# Sheet1.net
KiCad netlist of a schematic drawn in Altium Designer
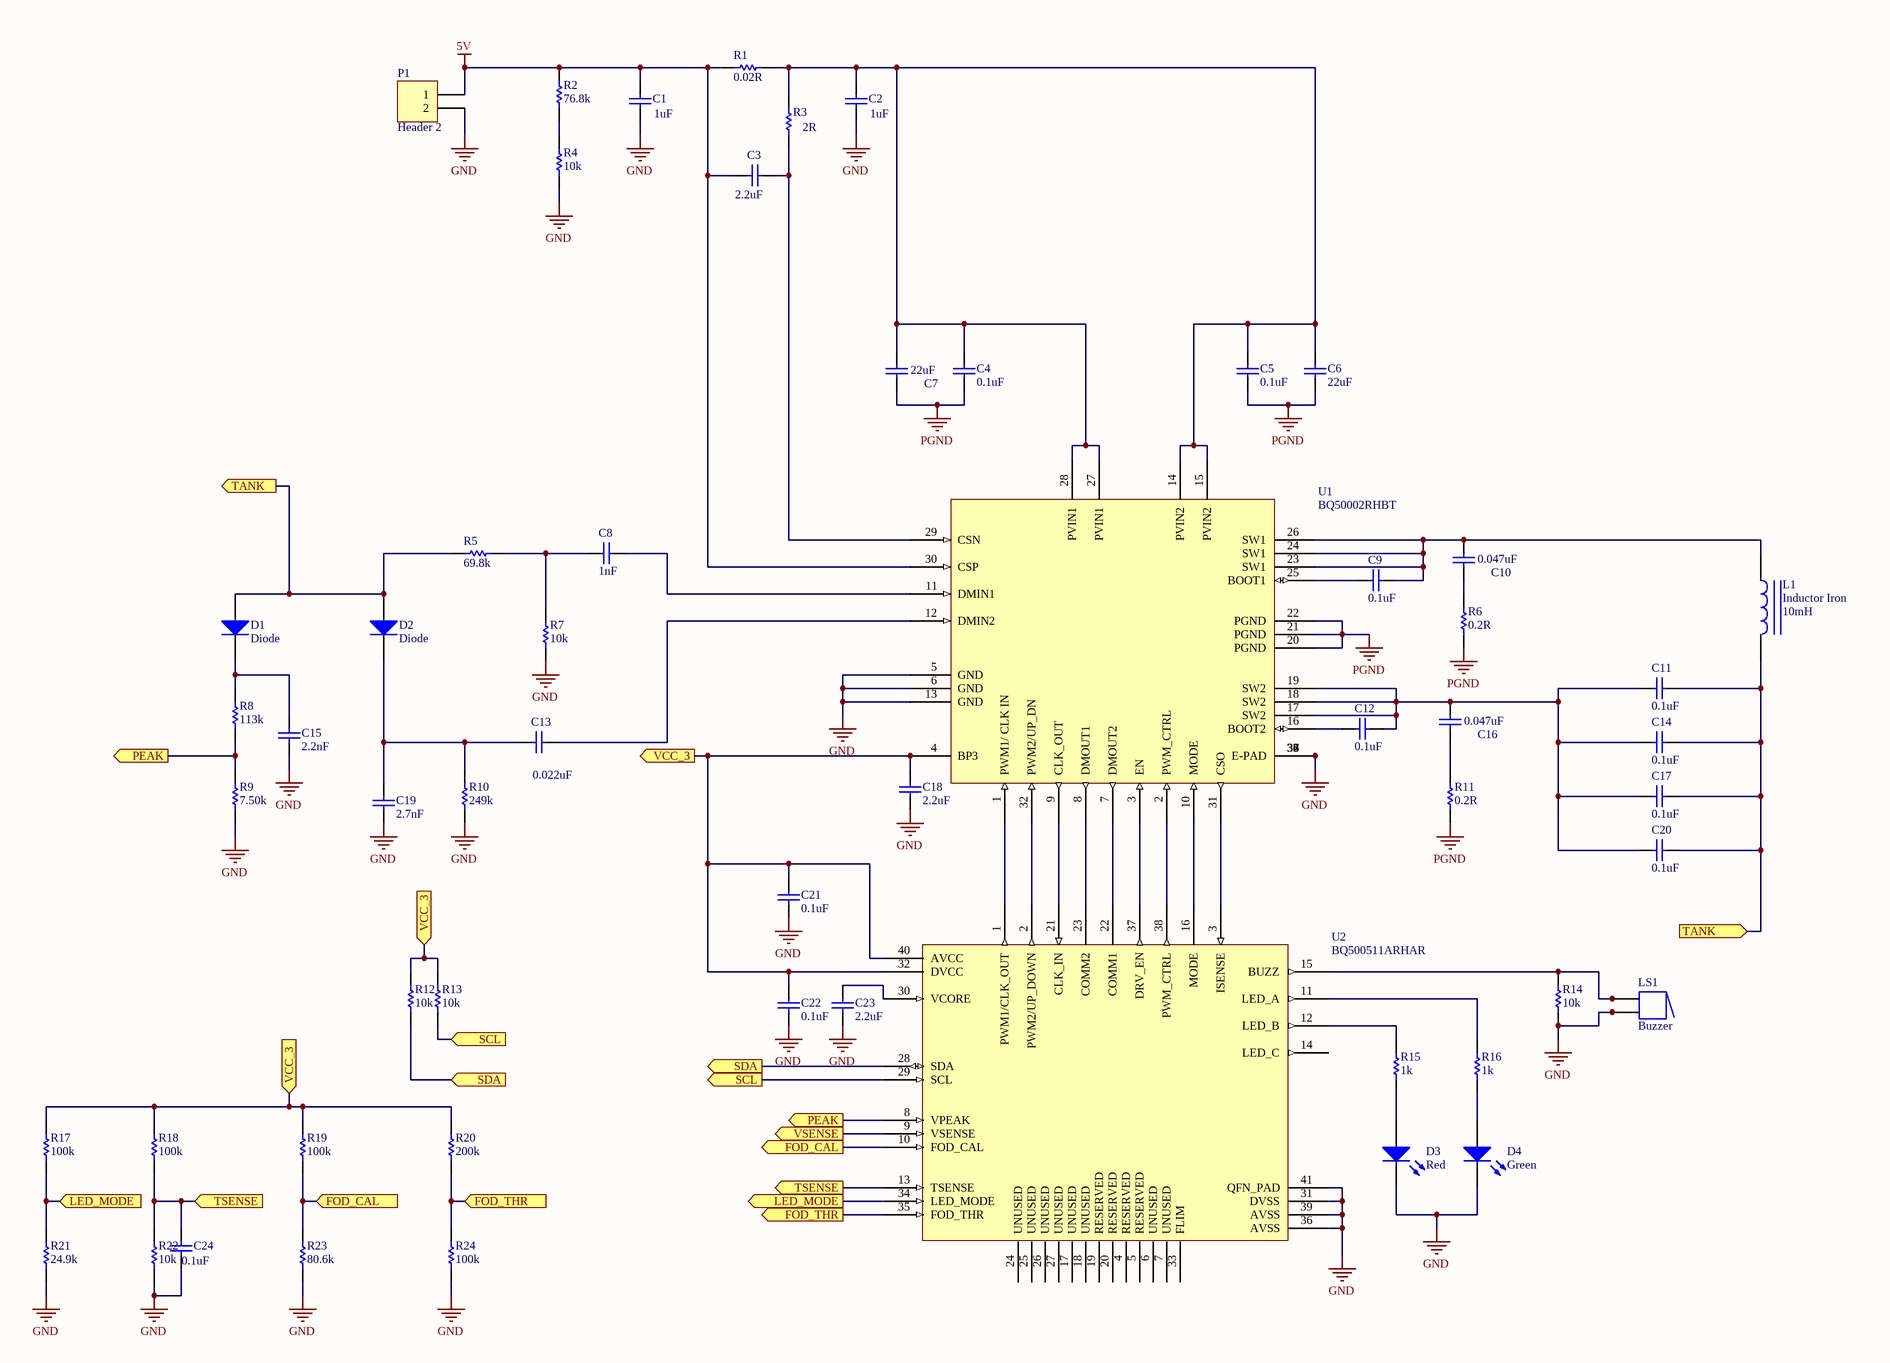
[diagram p0: Sheet1.SchDoc]

(export (version "E")
  (design (tool "Eeschema 10.0.6"))
  (components
    (comp (ref "C1")
      (value "1uF")
      (footprint "RAD-0.3")
      (description "Capacitor")
      (fields (field (name "PUBLISHER") "Altium Limited"))
      (libsource (lib "Miscellaneous Devices") (part "Cap"))
    )
    (comp (ref "C2")
      (value "1uF")
      (footprint "RAD-0.3")
      (description "Capacitor")
      (fields (field (name "PUBLISHER") "Altium Limited"))
      (libsource (lib "Miscellaneous Devices") (part "Cap"))
    )
    (comp (ref "C3")
      (value "2.2uF")
      (footprint "RAD-0.3")
      (description "Capacitor")
      (fields (field (name "PUBLISHER") "Altium Limited"))
      (libsource (lib "Miscellaneous Devices") (part "Cap"))
    )
    (comp (ref "C4")
      (value "0.1uF")
      (footprint "RAD-0.3")
      (description "Capacitor")
      (fields (field (name "PUBLISHER") "Altium Limited"))
      (libsource (lib "Miscellaneous Devices") (part "Cap"))
    )
    (comp (ref "C5")
      (value "0.1uF")
      (footprint "RAD-0.3")
      (description "Capacitor")
      (fields (field (name "PUBLISHER") "Altium Limited"))
      (libsource (lib "Miscellaneous Devices") (part "Cap"))
    )
    (comp (ref "C6")
      (value "22uF")
      (footprint "RAD-0.3")
      (description "Capacitor")
      (fields (field (name "PUBLISHER") "Altium Limited"))
      (libsource (lib "Miscellaneous Devices") (part "Cap"))
    )
    (comp (ref "C7")
      (value "22uF")
      (footprint "RAD-0.3")
      (description "Capacitor")
      (fields (field (name "PUBLISHER") "Altium Limited"))
      (libsource (lib "Miscellaneous Devices") (part "Cap"))
    )
    (comp (ref "C8")
      (value "1nF")
      (footprint "RAD-0.3")
      (description "Capacitor")
      (fields (field (name "PUBLISHER") "Altium Limited"))
      (libsource (lib "Miscellaneous Devices") (part "Cap"))
    )
    (comp (ref "C9")
      (value "0.1uF")
      (footprint "RAD-0.3")
      (description "Capacitor")
      (fields (field (name "PUBLISHER") "Altium Limited"))
      (libsource (lib "Miscellaneous Devices") (part "Cap"))
    )
    (comp (ref "C10")
      (value "0.047uF")
      (footprint "RAD-0.3")
      (description "Capacitor")
      (fields (field (name "PUBLISHER") "Altium Limited"))
      (libsource (lib "Miscellaneous Devices") (part "Cap"))
    )
    (comp (ref "C11")
      (value "0.1uF")
      (footprint "RAD-0.3")
      (description "Capacitor")
      (fields (field (name "PUBLISHER") "Altium Limited"))
      (libsource (lib "Miscellaneous Devices") (part "Cap"))
    )
    (comp (ref "C12")
      (value "0.1uF")
      (footprint "RAD-0.3")
      (description "Capacitor")
      (fields (field (name "PUBLISHER") "Altium Limited"))
      (libsource (lib "Miscellaneous Devices") (part "Cap"))
    )
    (comp (ref "C13")
      (value "0.022uF")
      (footprint "RAD-0.3")
      (description "Capacitor")
      (fields (field (name "PUBLISHER") "Altium Limited"))
      (libsource (lib "Miscellaneous Devices") (part "Cap"))
    )
    (comp (ref "C14")
      (value "0.1uF")
      (footprint "RAD-0.3")
      (description "Capacitor")
      (fields (field (name "PUBLISHER") "Altium Limited"))
      (libsource (lib "Miscellaneous Devices") (part "Cap"))
    )
    (comp (ref "C15")
      (value "2.2nF")
      (footprint "RAD-0.3")
      (description "Capacitor")
      (fields (field (name "PUBLISHER") "Altium Limited"))
      (libsource (lib "Miscellaneous Devices") (part "Cap"))
    )
    (comp (ref "C16")
      (value "0.047uF")
      (footprint "RAD-0.3")
      (description "Capacitor")
      (fields (field (name "PUBLISHER") "Altium Limited"))
      (libsource (lib "Miscellaneous Devices") (part "Cap"))
    )
    (comp (ref "C17")
      (value "0.1uF")
      (footprint "RAD-0.3")
      (description "Capacitor")
      (fields (field (name "PUBLISHER") "Altium Limited"))
      (libsource (lib "Miscellaneous Devices") (part "Cap"))
    )
    (comp (ref "C18")
      (value "2.2uF")
      (footprint "RAD-0.3")
      (description "Capacitor")
      (fields (field (name "PUBLISHER") "Altium Limited"))
      (libsource (lib "Miscellaneous Devices") (part "Cap"))
    )
    (comp (ref "C19")
      (value "2.7nF")
      (footprint "RAD-0.3")
      (description "Capacitor")
      (fields (field (name "PUBLISHER") "Altium Limited"))
      (libsource (lib "Miscellaneous Devices") (part "Cap"))
    )
    (comp (ref "C20")
      (value "0.1uF")
      (footprint "RAD-0.3")
      (description "Capacitor")
      (fields (field (name "PUBLISHER") "Altium Limited"))
      (libsource (lib "Miscellaneous Devices") (part "Cap"))
    )
    (comp (ref "C21")
      (value "0.1uF")
      (footprint "RAD-0.3")
      (description "Capacitor")
      (fields (field (name "PUBLISHER") "Altium Limited"))
      (libsource (lib "Miscellaneous Devices") (part "Cap"))
    )
    (comp (ref "C22")
      (value "0.1uF")
      (footprint "RAD-0.3")
      (description "Capacitor")
      (fields (field (name "PUBLISHER") "Altium Limited"))
      (libsource (lib "Miscellaneous Devices") (part "Cap"))
    )
    (comp (ref "C23")
      (value "2.2uF")
      (footprint "RAD-0.3")
      (description "Capacitor")
      (fields (field (name "PUBLISHER") "Altium Limited"))
      (libsource (lib "Miscellaneous Devices") (part "Cap"))
    )
    (comp (ref "C24")
      (value "0.1uF")
      (footprint "RAD-0.3")
      (description "Capacitor")
      (fields (field (name "PUBLISHER") "Altium Limited"))
      (libsource (lib "Miscellaneous Devices") (part "Cap"))
    )
    (comp (ref "D1")
      (value "Diode")
      (footprint "SMC")
      (description "Default Diode")
      (fields (field (name "PUBLISHER") "Altium Limited"))
      (libsource (lib "Miscellaneous Devices") (part "Diode"))
    )
    (comp (ref "D2")
      (value "Diode")
      (footprint "SMC")
      (description "Default Diode")
      (fields (field (name "PUBLISHER") "Altium Limited"))
      (libsource (lib "Miscellaneous Devices") (part "Diode"))
    )
    (comp (ref "D3")
      (value "Red")
      (footprint "LED-1")
      (description "Typical RED GaAs LED")
      (fields (field (name "PUBLISHER") "Altium Limited"))
      (libsource (lib "Miscellaneous Devices") (part "LED1"))
    )
    (comp (ref "D4")
      (value "Green")
      (footprint "LED-1")
      (description "Typical RED GaAs LED")
      (fields (field (name "PUBLISHER") "Altium Limited"))
      (libsource (lib "Miscellaneous Devices") (part "LED1"))
    )
    (comp (ref "L1")
      (value "Inductor Iron")
      (footprint "AXIAL-0.9")
      (description "Magnetic-Core Inductor")
      (fields (field (name "ALTIUM_VALUE") "10mH") (field (name "PUBLISHER") "Altium Limited"))
      (libsource (lib "Miscellaneous Devices") (part "Inductor Iron"))
    )
    (comp (ref "LS1")
      (value "Buzzer")
      (footprint "ABSM-1574")
      (description "Magnetic Transducer Buzzer")
      (fields (field (name "PUBLISHER") "Altium Limited"))
      (libsource (lib "Miscellaneous Devices") (part "Buzzer"))
    )
    (comp (ref "P1")
      (value "Header 2")
      (footprint "HDR1X2")
      (description "Header, 2-Pin")
      (fields (field (name "PUBLISHER") "Altium Limited"))
      (libsource (lib "Miscellaneous Connectors") (part "Header 2"))
    )
    (comp (ref "R1")
      (value "0.02R")
      (footprint "AXIAL-0.3")
      (description "Resistor")
      (fields (field (name "PUBLISHER") "Altium Limited"))
      (libsource (lib "Miscellaneous Devices") (part "Res1"))
    )
    (comp (ref "R2")
      (value "76.8k")
      (footprint "AXIAL-0.3")
      (description "Resistor")
      (fields (field (name "PUBLISHER") "Altium Limited"))
      (libsource (lib "Miscellaneous Devices") (part "Res1"))
    )
    (comp (ref "R3")
      (value "2R")
      (footprint "AXIAL-0.3")
      (description "Resistor")
      (fields (field (name "PUBLISHER") "Altium Limited"))
      (libsource (lib "Miscellaneous Devices") (part "Res1"))
    )
    (comp (ref "R4")
      (value "10k")
      (footprint "AXIAL-0.3")
      (description "Resistor")
      (fields (field (name "PUBLISHER") "Altium Limited"))
      (libsource (lib "Miscellaneous Devices") (part "Res1"))
    )
    (comp (ref "R5")
      (value "69.8k")
      (footprint "AXIAL-0.3")
      (description "Resistor")
      (fields (field (name "PUBLISHER") "Altium Limited"))
      (libsource (lib "Miscellaneous Devices") (part "Res1"))
    )
    (comp (ref "R6")
      (value "0.2R")
      (footprint "AXIAL-0.3")
      (description "Resistor")
      (fields (field (name "PUBLISHER") "Altium Limited"))
      (libsource (lib "Miscellaneous Devices") (part "Res1"))
    )
    (comp (ref "R7")
      (value "10k")
      (footprint "AXIAL-0.3")
      (description "Resistor")
      (fields (field (name "PUBLISHER") "Altium Limited"))
      (libsource (lib "Miscellaneous Devices") (part "Res1"))
    )
    (comp (ref "R8")
      (value "113k")
      (footprint "AXIAL-0.3")
      (description "Resistor")
      (fields (field (name "PUBLISHER") "Altium Limited"))
      (libsource (lib "Miscellaneous Devices") (part "Res1"))
    )
    (comp (ref "R9")
      (value "7.50k")
      (footprint "AXIAL-0.3")
      (description "Resistor")
      (fields (field (name "PUBLISHER") "Altium Limited"))
      (libsource (lib "Miscellaneous Devices") (part "Res1"))
    )
    (comp (ref "R10")
      (value "249k")
      (footprint "AXIAL-0.3")
      (description "Resistor")
      (fields (field (name "PUBLISHER") "Altium Limited"))
      (libsource (lib "Miscellaneous Devices") (part "Res1"))
    )
    (comp (ref "R11")
      (value "0.2R")
      (footprint "AXIAL-0.3")
      (description "Resistor")
      (fields (field (name "PUBLISHER") "Altium Limited"))
      (libsource (lib "Miscellaneous Devices") (part "Res1"))
    )
    (comp (ref "R12")
      (value "10k")
      (footprint "AXIAL-0.3")
      (description "Resistor")
      (fields (field (name "PUBLISHER") "Altium Limited"))
      (libsource (lib "Miscellaneous Devices") (part "Res1"))
    )
    (comp (ref "R13")
      (value "10k")
      (footprint "AXIAL-0.3")
      (description "Resistor")
      (fields (field (name "PUBLISHER") "Altium Limited"))
      (libsource (lib "Miscellaneous Devices") (part "Res1"))
    )
    (comp (ref "R14")
      (value "10k")
      (footprint "AXIAL-0.3")
      (description "Resistor")
      (fields (field (name "PUBLISHER") "Altium Limited"))
      (libsource (lib "Miscellaneous Devices") (part "Res1"))
    )
    (comp (ref "R15")
      (value "1k")
      (footprint "AXIAL-0.3")
      (description "Resistor")
      (fields (field (name "PUBLISHER") "Altium Limited"))
      (libsource (lib "Miscellaneous Devices") (part "Res1"))
    )
    (comp (ref "R16")
      (value "1k")
      (footprint "AXIAL-0.3")
      (description "Resistor")
      (fields (field (name "PUBLISHER") "Altium Limited"))
      (libsource (lib "Miscellaneous Devices") (part "Res1"))
    )
    (comp (ref "R17")
      (value "100k")
      (footprint "AXIAL-0.3")
      (description "Resistor")
      (fields (field (name "PUBLISHER") "Altium Limited"))
      (libsource (lib "Miscellaneous Devices") (part "Res1"))
    )
    (comp (ref "R18")
      (value "100k")
      (footprint "AXIAL-0.3")
      (description "Resistor")
      (fields (field (name "PUBLISHER") "Altium Limited"))
      (libsource (lib "Miscellaneous Devices") (part "Res1"))
    )
    (comp (ref "R19")
      (value "100k")
      (footprint "AXIAL-0.3")
      (description "Resistor")
      (fields (field (name "PUBLISHER") "Altium Limited"))
      (libsource (lib "Miscellaneous Devices") (part "Res1"))
    )
    (comp (ref "R20")
      (value "200k")
      (footprint "AXIAL-0.3")
      (description "Resistor")
      (fields (field (name "PUBLISHER") "Altium Limited"))
      (libsource (lib "Miscellaneous Devices") (part "Res1"))
    )
    (comp (ref "R21")
      (value "24.9k")
      (footprint "AXIAL-0.3")
      (description "Resistor")
      (fields (field (name "PUBLISHER") "Altium Limited"))
      (libsource (lib "Miscellaneous Devices") (part "Res1"))
    )
    (comp (ref "R22")
      (value "10k")
      (footprint "AXIAL-0.3")
      (description "Resistor")
      (fields (field (name "PUBLISHER") "Altium Limited"))
      (libsource (lib "Miscellaneous Devices") (part "Res1"))
    )
    (comp (ref "R23")
      (value "80.6k")
      (footprint "AXIAL-0.3")
      (description "Resistor")
      (fields (field (name "PUBLISHER") "Altium Limited"))
      (libsource (lib "Miscellaneous Devices") (part "Res1"))
    )
    (comp (ref "R24")
      (value "100k")
      (footprint "AXIAL-0.3")
      (description "Resistor")
      (fields (field (name "PUBLISHER") "Altium Limited"))
      (libsource (lib "Miscellaneous Devices") (part "Res1"))
    )
    (comp (ref "U1")
      (value "BQ50002RHBT")
      (footprint "BQ50002_VQFN-32")
      (description "Wireless Charging ICs Wireless Power Transmitter Analog Front End 32-VQFN -40 to 125")
      (fields (field (name "MANUFACTURER") "Texas Instruments"))
      (libsource (lib "Schlib1") (part "BQ50002RHBT"))
    )
    (comp (ref "U2")
      (value "BQ500511ARHAR")
      (footprint "QFN50P600X600X100-41N")
      (description "Wireless Power Transmitter Controller 40-VQFN -40 to 85")
      (fields (field (name "MANUFACTURER") "Texas Instruments"))
      (libsource (lib "Schlib1") (part "BQ500511ARHAR"))
    )
  )
  (nets
    (net (code "1") (name "/FOD_CAL") (class "Default")
      (node (ref "R19") (pin "2") (pinfunction "2_2") (pintype "passive"))
      (node (ref "R23") (pin "1") (pinfunction "1_1") (pintype "passive"))
      (node (ref "U2") (pin "10") (pinfunction "FOD_CAL_10") (pintype "input"))
    )
    (net (code "2") (name "/FOD_THR") (class "Default")
      (node (ref "R20") (pin "2") (pinfunction "2_2") (pintype "passive"))
      (node (ref "R24") (pin "1") (pinfunction "1_1") (pintype "passive"))
      (node (ref "U2") (pin "35") (pinfunction "FOD_THR_35") (pintype "input"))
    )
    (net (code "3") (name "/LED_MODE") (class "Default")
      (node (ref "R17") (pin "2") (pinfunction "2_2") (pintype "passive"))
      (node (ref "R21") (pin "1") (pinfunction "1_1") (pintype "passive"))
      (node (ref "U2") (pin "34") (pinfunction "LED_MODE_34") (pintype "input"))
    )
    (net (code "4") (name "/PEAK") (class "Default")
      (node (ref "R8") (pin "2") (pinfunction "2_2") (pintype "passive"))
      (node (ref "R9") (pin "1") (pinfunction "1_1") (pintype "passive"))
      (node (ref "U2") (pin "8") (pinfunction "VPEAK_8") (pintype "input"))
    )
    (net (code "5") (name "/SCL") (class "Default")
      (node (ref "R13") (pin "1") (pinfunction "1_1") (pintype "passive"))
      (node (ref "U2") (pin "29") (pinfunction "SCL_29") (pintype "input"))
    )
    (net (code "6") (name "/SDA") (class "Default")
      (node (ref "R12") (pin "1") (pinfunction "1_1") (pintype "passive"))
      (node (ref "U2") (pin "28") (pinfunction "SDA_28") (pintype "bidirectional"))
    )
    (net (code "7") (name "/TANK") (class "Default")
      (node (ref "C11") (pin "1") (pinfunction "1_1") (pintype "passive"))
      (node (ref "C14") (pin "1") (pinfunction "1_1") (pintype "passive"))
      (node (ref "C17") (pin "1") (pinfunction "1_1") (pintype "passive"))
      (node (ref "C20") (pin "1") (pinfunction "1_1") (pintype "passive"))
      (node (ref "D1") (pin "1") (pinfunction "A_1") (pintype "passive"))
      (node (ref "D2") (pin "1") (pinfunction "A_1") (pintype "passive"))
      (node (ref "L1") (pin "2") (pinfunction "2_2") (pintype "passive"))
      (node (ref "R5") (pin "1") (pinfunction "1_1") (pintype "passive"))
    )
    (net (code "8") (name "/TSENSE") (class "Default")
      (node (ref "C24") (pin "1") (pinfunction "1_1") (pintype "passive"))
      (node (ref "R18") (pin "2") (pinfunction "2_2") (pintype "passive"))
      (node (ref "R22") (pin "1") (pinfunction "1_1") (pintype "passive"))
      (node (ref "U2") (pin "13") (pinfunction "TSENSE_13") (pintype "input"))
    )
    (net (code "9") (name "/VCC_3") (class "Default")
      (node (ref "C18") (pin "1") (pinfunction "1_1") (pintype "passive"))
      (node (ref "C21") (pin "1") (pinfunction "1_1") (pintype "passive"))
      (node (ref "C22") (pin "1") (pinfunction "1_1") (pintype "passive"))
      (node (ref "R12") (pin "2") (pinfunction "2_2") (pintype "passive"))
      (node (ref "R13") (pin "2") (pinfunction "2_2") (pintype "passive"))
      (node (ref "R17") (pin "1") (pinfunction "1_1") (pintype "passive"))
      (node (ref "R18") (pin "1") (pinfunction "1_1") (pintype "passive"))
      (node (ref "R19") (pin "1") (pinfunction "1_1") (pintype "passive"))
      (node (ref "R20") (pin "1") (pinfunction "1_1") (pintype "passive"))
      (node (ref "U1") (pin "4") (pinfunction "BP3_4") (pintype "passive"))
      (node (ref "U2") (pin "32") (pinfunction "DVCC_32") (pintype "power_in"))
      (node (ref "U2") (pin "40") (pinfunction "AVCC_40") (pintype "power_in"))
    )
    (net (code "10") (name "/VSENSE") (class "Default")
      (node (ref "U2") (pin "9") (pinfunction "VSENSE_9") (pintype "input"))
    )
    (net (code "11") (name "5V") (class "Default")
      (node (ref "C1") (pin "2") (pinfunction "2_2") (pintype "passive"))
      (node (ref "C3") (pin "2") (pinfunction "2_2") (pintype "passive"))
      (node (ref "P1") (pin "1") (pinfunction "1_1") (pintype "passive"))
      (node (ref "R1") (pin "1") (pinfunction "1_1") (pintype "passive"))
      (node (ref "R2") (pin "1") (pinfunction "1_1") (pintype "passive"))
      (node (ref "U1") (pin "30") (pinfunction "CSP_30") (pintype "input"))
    )
    (net (code "12") (name "GND") (class "Default")
      (node (ref "C1") (pin "1") (pinfunction "1_1") (pintype "passive"))
      (node (ref "C15") (pin "2") (pinfunction "2_2") (pintype "passive"))
      (node (ref "C18") (pin "2") (pinfunction "2_2") (pintype "passive"))
      (node (ref "C19") (pin "2") (pinfunction "2_2") (pintype "passive"))
      (node (ref "C2") (pin "1") (pinfunction "1_1") (pintype "passive"))
      (node (ref "C21") (pin "2") (pinfunction "2_2") (pintype "passive"))
      (node (ref "C22") (pin "2") (pinfunction "2_2") (pintype "passive"))
      (node (ref "C23") (pin "2") (pinfunction "2_2") (pintype "passive"))
      (node (ref "C24") (pin "2") (pinfunction "2_2") (pintype "passive"))
      (node (ref "D3") (pin "2") (pinfunction "K_2") (pintype "passive"))
      (node (ref "D4") (pin "2") (pinfunction "K_2") (pintype "passive"))
      (node (ref "LS1") (pin "2") (pinfunction "2_2") (pintype "passive"))
      (node (ref "LS1") (pin "2A") (pinfunction "2A_2A") (pintype "passive"))
      (node (ref "P1") (pin "2") (pinfunction "2_2") (pintype "passive"))
      (node (ref "R10") (pin "2") (pinfunction "2_2") (pintype "passive"))
      (node (ref "R14") (pin "1") (pinfunction "1_1") (pintype "passive"))
      (node (ref "R21") (pin "2") (pinfunction "2_2") (pintype "passive"))
      (node (ref "R22") (pin "2") (pinfunction "2_2") (pintype "passive"))
      (node (ref "R23") (pin "2") (pinfunction "2_2") (pintype "passive"))
      (node (ref "R24") (pin "2") (pinfunction "2_2") (pintype "passive"))
      (node (ref "R4") (pin "2") (pinfunction "2_2") (pintype "passive"))
      (node (ref "R7") (pin "2") (pinfunction "2_2") (pintype "passive"))
      (node (ref "R9") (pin "2") (pinfunction "2_2") (pintype "passive"))
      (node (ref "U1") (pin "13") (pinfunction "GND_13") (pintype "power_in"))
      (node (ref "U1") (pin "33") (pinfunction "E-PAD_33") (pintype "passive"))
      (node (ref "U1") (pin "34") (pinfunction "34_34") (pintype "passive"))
      (node (ref "U1") (pin "35") (pinfunction "35_35") (pintype "passive"))
      (node (ref "U1") (pin "36") (pinfunction "36_36") (pintype "passive"))
      (node (ref "U1") (pin "37") (pinfunction "37_37") (pintype "passive"))
      (node (ref "U1") (pin "38") (pinfunction "38_38") (pintype "passive"))
      (node (ref "U1") (pin "5") (pinfunction "GND_5") (pintype "power_in"))
      (node (ref "U1") (pin "6") (pinfunction "GND_6") (pintype "power_in"))
      (node (ref "U2") (pin "31") (pinfunction "DVSS_31") (pintype "power_in"))
      (node (ref "U2") (pin "36") (pinfunction "AVSS_36") (pintype "power_in"))
      (node (ref "U2") (pin "39") (pinfunction "AVSS_39") (pintype "power_in"))
      (node (ref "U2") (pin "41") (pinfunction "QFN_PAD_41") (pintype "power_in"))
    )
    (net (code "13") (name "Net-(C2-Pad2)") (class "Default")
      (node (ref "C2") (pin "2") (pinfunction "2_2") (pintype "passive"))
      (node (ref "C4") (pin "1") (pinfunction "1_1") (pintype "passive"))
      (node (ref "C5") (pin "1") (pinfunction "1_1") (pintype "passive"))
      (node (ref "C6") (pin "1") (pinfunction "1_1") (pintype "passive"))
      (node (ref "C7") (pin "2") (pinfunction "2_2") (pintype "passive"))
      (node (ref "R1") (pin "2") (pinfunction "2_2") (pintype "passive"))
      (node (ref "R3") (pin "2") (pinfunction "2_2") (pintype "passive"))
      (node (ref "U1") (pin "14") (pinfunction "PVIN2_14") (pintype "power_in"))
      (node (ref "U1") (pin "15") (pinfunction "PVIN2_15") (pintype "power_in"))
      (node (ref "U1") (pin "27") (pinfunction "PVIN1_27") (pintype "power_in"))
      (node (ref "U1") (pin "28") (pinfunction "PVIN1_28") (pintype "power_in"))
    )
    (net (code "14") (name "Net-(C8-Pad2)") (class "Default")
      (node (ref "C8") (pin "2") (pinfunction "2_2") (pintype "passive"))
      (node (ref "R5") (pin "2") (pinfunction "2_2") (pintype "passive"))
      (node (ref "R7") (pin "1") (pinfunction "1_1") (pintype "passive"))
    )
    (net (code "15") (name "Net-(C10-Pad1)") (class "Default")
      (node (ref "C10") (pin "1") (pinfunction "1_1") (pintype "passive"))
      (node (ref "R6") (pin "1") (pinfunction "1_1") (pintype "passive"))
    )
    (net (code "16") (name "Net-(C10-Pad2)") (class "Default")
      (node (ref "C10") (pin "2") (pinfunction "2_2") (pintype "passive"))
      (node (ref "C9") (pin "1") (pinfunction "1_1") (pintype "passive"))
      (node (ref "L1") (pin "1") (pinfunction "1_1") (pintype "passive"))
      (node (ref "U1") (pin "23") (pinfunction "SW1_23") (pintype "power_in"))
      (node (ref "U1") (pin "24") (pinfunction "SW1_24") (pintype "power_in"))
      (node (ref "U1") (pin "26") (pinfunction "SW1_26") (pintype "power_in"))
    )
    (net (code "17") (name "Net-(C11-Pad2)") (class "Default")
      (node (ref "C11") (pin "2") (pinfunction "2_2") (pintype "passive"))
      (node (ref "C12") (pin "1") (pinfunction "1_1") (pintype "passive"))
      (node (ref "C14") (pin "2") (pinfunction "2_2") (pintype "passive"))
      (node (ref "C16") (pin "2") (pinfunction "2_2") (pintype "passive"))
      (node (ref "C17") (pin "2") (pinfunction "2_2") (pintype "passive"))
      (node (ref "C20") (pin "2") (pinfunction "2_2") (pintype "passive"))
      (node (ref "U1") (pin "17") (pinfunction "SW2_17") (pintype "power_in"))
      (node (ref "U1") (pin "18") (pinfunction "SW2_18") (pintype "power_in"))
      (node (ref "U1") (pin "19") (pinfunction "SW2_19") (pintype "power_in"))
    )
    (net (code "18") (name "Net-(C16-Pad1)") (class "Default")
      (node (ref "C16") (pin "1") (pinfunction "1_1") (pintype "passive"))
      (node (ref "R11") (pin "1") (pinfunction "1_1") (pintype "passive"))
    )
    (net (code "19") (name "Net-(D1-K)") (class "Default")
      (node (ref "C15") (pin "1") (pinfunction "1_1") (pintype "passive"))
      (node (ref "D1") (pin "2") (pinfunction "K_2") (pintype "passive"))
      (node (ref "R8") (pin "1") (pinfunction "1_1") (pintype "passive"))
    )
    (net (code "20") (name "Net-(D2-K)") (class "Default")
      (node (ref "C13") (pin "1") (pinfunction "1_1") (pintype "passive"))
      (node (ref "C19") (pin "1") (pinfunction "1_1") (pintype "passive"))
      (node (ref "D2") (pin "2") (pinfunction "K_2") (pintype "passive"))
      (node (ref "R10") (pin "1") (pinfunction "1_1") (pintype "passive"))
    )
    (net (code "21") (name "Net-(D3-A)") (class "Default")
      (node (ref "D3") (pin "1") (pinfunction "A_1") (pintype "passive"))
      (node (ref "R15") (pin "1") (pinfunction "1_1") (pintype "passive"))
    )
    (net (code "22") (name "Net-(D4-A)") (class "Default")
      (node (ref "D4") (pin "1") (pinfunction "A_1") (pintype "passive"))
      (node (ref "R16") (pin "1") (pinfunction "1_1") (pintype "passive"))
    )
    (net (code "23") (name "Net-(R2-Pad2)") (class "Default")
      (node (ref "R2") (pin "2") (pinfunction "2_2") (pintype "passive"))
      (node (ref "R4") (pin "1") (pinfunction "1_1") (pintype "passive"))
    )
    (net (code "24") (name "Net-(U1-BOOT1)") (class "Default")
      (node (ref "C9") (pin "2") (pinfunction "2_2") (pintype "passive"))
      (node (ref "U1") (pin "25") (pinfunction "BOOT1_25") (pintype "bidirectional"))
    )
    (net (code "25") (name "Net-(U1-BOOT2)") (class "Default")
      (node (ref "C12") (pin "2") (pinfunction "2_2") (pintype "passive"))
      (node (ref "U1") (pin "16") (pinfunction "BOOT2_16") (pintype "bidirectional"))
    )
    (net (code "26") (name "Net-(U1-CLK_OUT)") (class "Default")
      (node (ref "U1") (pin "9") (pinfunction "CLK_OUT_9") (pintype "output"))
      (node (ref "U2") (pin "21") (pinfunction "CLK_IN_21") (pintype "input"))
    )
    (net (code "27") (name "Net-(U1-CSN)") (class "Default")
      (node (ref "C3") (pin "1") (pinfunction "1_1") (pintype "passive"))
      (node (ref "R3") (pin "1") (pinfunction "1_1") (pintype "passive"))
      (node (ref "U1") (pin "29") (pinfunction "CSN_29") (pintype "input"))
    )
    (net (code "28") (name "Net-(U1-CSO)") (class "Default")
      (node (ref "U1") (pin "31") (pinfunction "CSO_31") (pintype "output"))
      (node (ref "U2") (pin "3") (pinfunction "ISENSE_3") (pintype "input"))
    )
    (net (code "29") (name "Net-(U1-DMIN1)") (class "Default")
      (node (ref "C8") (pin "1") (pinfunction "1_1") (pintype "passive"))
      (node (ref "U1") (pin "11") (pinfunction "DMIN1_11") (pintype "input"))
    )
    (net (code "30") (name "Net-(U1-DMIN2)") (class "Default")
      (node (ref "C13") (pin "2") (pinfunction "2_2") (pintype "passive"))
      (node (ref "U1") (pin "12") (pinfunction "DMIN2_12") (pintype "input"))
    )
    (net (code "31") (name "Net-(U1-DMOUT1)") (class "Default")
      (node (ref "U1") (pin "8") (pinfunction "DMOUT1_8") (pintype "output"))
      (node (ref "U2") (pin "23") (pinfunction "COMM2_23") (pintype "passive"))
    )
    (net (code "32") (name "Net-(U1-DMOUT2)") (class "Default")
      (node (ref "U1") (pin "7") (pinfunction "DMOUT2_7") (pintype "output"))
      (node (ref "U2") (pin "22") (pinfunction "COMM1_22") (pintype "passive"))
    )
    (net (code "33") (name "Net-(U1-EN)") (class "Default")
      (node (ref "U1") (pin "3") (pinfunction "EN_3") (pintype "input"))
      (node (ref "U2") (pin "37") (pinfunction "DRV_EN_37") (pintype "output"))
    )
    (net (code "34") (name "Net-(U1-MODE)") (class "Default")
      (node (ref "U1") (pin "10") (pinfunction "MODE_10") (pintype "input"))
      (node (ref "U2") (pin "16") (pinfunction "MODE_16") (pintype "passive"))
    )
    (net (code "35") (name "Net-(U1-PWM1{slash}_CLK_IN)") (class "Default")
      (node (ref "U1") (pin "1") (pinfunction "PWM1/_CLK_IN_1") (pintype "input"))
      (node (ref "U2") (pin "1") (pinfunction "PWM1/CLK_OUT_1") (pintype "output"))
    )
    (net (code "36") (name "Net-(U1-PWM2{slash}UP_DN)") (class "Default")
      (node (ref "U1") (pin "32") (pinfunction "PWM2/UP_DN_32") (pintype "input"))
      (node (ref "U2") (pin "2") (pinfunction "PWM2/UP_DOWN_2") (pintype "output"))
    )
    (net (code "37") (name "Net-(U1-PWM_CTRL)") (class "Default")
      (node (ref "U1") (pin "2") (pinfunction "PWM_CTRL_2") (pintype "input"))
      (node (ref "U2") (pin "38") (pinfunction "PWM_CTRL_38") (pintype "output"))
    )
    (net (code "38") (name "Net-(U2-BUZZ)") (class "Default")
      (node (ref "LS1") (pin "1") (pinfunction "1_1") (pintype "passive"))
      (node (ref "LS1") (pin "1A") (pinfunction "1A_1A") (pintype "passive"))
      (node (ref "R14") (pin "2") (pinfunction "2_2") (pintype "passive"))
      (node (ref "U2") (pin "15") (pinfunction "BUZZ_15") (pintype "output"))
    )
    (net (code "39") (name "Net-(U2-LED_A)") (class "Default")
      (node (ref "R16") (pin "2") (pinfunction "2_2") (pintype "passive"))
      (node (ref "U2") (pin "11") (pinfunction "LED_A_11") (pintype "output"))
    )
    (net (code "40") (name "Net-(U2-LED_B)") (class "Default")
      (node (ref "R15") (pin "2") (pinfunction "2_2") (pintype "passive"))
      (node (ref "U2") (pin "12") (pinfunction "LED_B_12") (pintype "output"))
    )
    (net (code "41") (name "Net-(U2-VCORE)") (class "Default")
      (node (ref "C23") (pin "1") (pinfunction "1_1") (pintype "passive"))
      (node (ref "U2") (pin "30") (pinfunction "VCORE_30") (pintype "input"))
    )
    (net (code "42") (name "PGND") (class "Default")
      (node (ref "C4") (pin "2") (pinfunction "2_2") (pintype "passive"))
      (node (ref "C5") (pin "2") (pinfunction "2_2") (pintype "passive"))
      (node (ref "C6") (pin "2") (pinfunction "2_2") (pintype "passive"))
      (node (ref "C7") (pin "1") (pinfunction "1_1") (pintype "passive"))
      (node (ref "R11") (pin "2") (pinfunction "2_2") (pintype "passive"))
      (node (ref "R6") (pin "2") (pinfunction "2_2") (pintype "passive"))
      (node (ref "U1") (pin "20") (pinfunction "PGND_20") (pintype "power_in"))
      (node (ref "U1") (pin "21") (pinfunction "PGND_21") (pintype "power_in"))
      (node (ref "U1") (pin "22") (pinfunction "PGND_22") (pintype "power_in"))
    )
    (net (code "43") (name "unconnected-(U2-FLIM-Pad33)") (class "Default")
      (node (ref "U2") (pin "33") (pinfunction "FLIM_33") (pintype "passive"))
    )
    (net (code "44") (name "unconnected-(U2-LED_C-Pad14)") (class "Default")
      (node (ref "U2") (pin "14") (pinfunction "LED_C_14") (pintype "output"))
    )
    (net (code "45") (name "unconnected-(U2-RESERVED-Pad4)") (class "Default")
      (node (ref "U2") (pin "4") (pinfunction "RESERVED_4") (pintype "passive"))
    )
    (net (code "46") (name "unconnected-(U2-RESERVED-Pad5)") (class "Default")
      (node (ref "U2") (pin "5") (pinfunction "RESERVED_5") (pintype "passive"))
    )
    (net (code "47") (name "unconnected-(U2-RESERVED-Pad19)") (class "Default")
      (node (ref "U2") (pin "19") (pinfunction "RESERVED_19") (pintype "passive"))
    )
    (net (code "48") (name "unconnected-(U2-RESERVED-Pad20)") (class "Default")
      (node (ref "U2") (pin "20") (pinfunction "RESERVED_20") (pintype "passive"))
    )
    (net (code "49") (name "unconnected-(U2-UNUSED-Pad6)") (class "Default")
      (node (ref "U2") (pin "6") (pinfunction "UNUSED_6") (pintype "passive"))
    )
    (net (code "50") (name "unconnected-(U2-UNUSED-Pad7)") (class "Default")
      (node (ref "U2") (pin "7") (pinfunction "UNUSED_7") (pintype "passive"))
    )
    (net (code "51") (name "unconnected-(U2-UNUSED-Pad17)") (class "Default")
      (node (ref "U2") (pin "17") (pinfunction "UNUSED_17") (pintype "passive"))
    )
    (net (code "52") (name "unconnected-(U2-UNUSED-Pad18)") (class "Default")
      (node (ref "U2") (pin "18") (pinfunction "UNUSED_18") (pintype "passive"))
    )
    (net (code "53") (name "unconnected-(U2-UNUSED-Pad24)") (class "Default")
      (node (ref "U2") (pin "24") (pinfunction "UNUSED_24") (pintype "passive"))
    )
    (net (code "54") (name "unconnected-(U2-UNUSED-Pad25)") (class "Default")
      (node (ref "U2") (pin "25") (pinfunction "UNUSED_25") (pintype "passive"))
    )
    (net (code "55") (name "unconnected-(U2-UNUSED-Pad26)") (class "Default")
      (node (ref "U2") (pin "26") (pinfunction "UNUSED_26") (pintype "passive"))
    )
    (net (code "56") (name "unconnected-(U2-UNUSED-Pad27)") (class "Default")
      (node (ref "U2") (pin "27") (pinfunction "UNUSED_27") (pintype "passive"))
    )
  )
)
